# RedLightFlashlightInsert.net
KiCad netlist of a schematic drawn in EAGLE
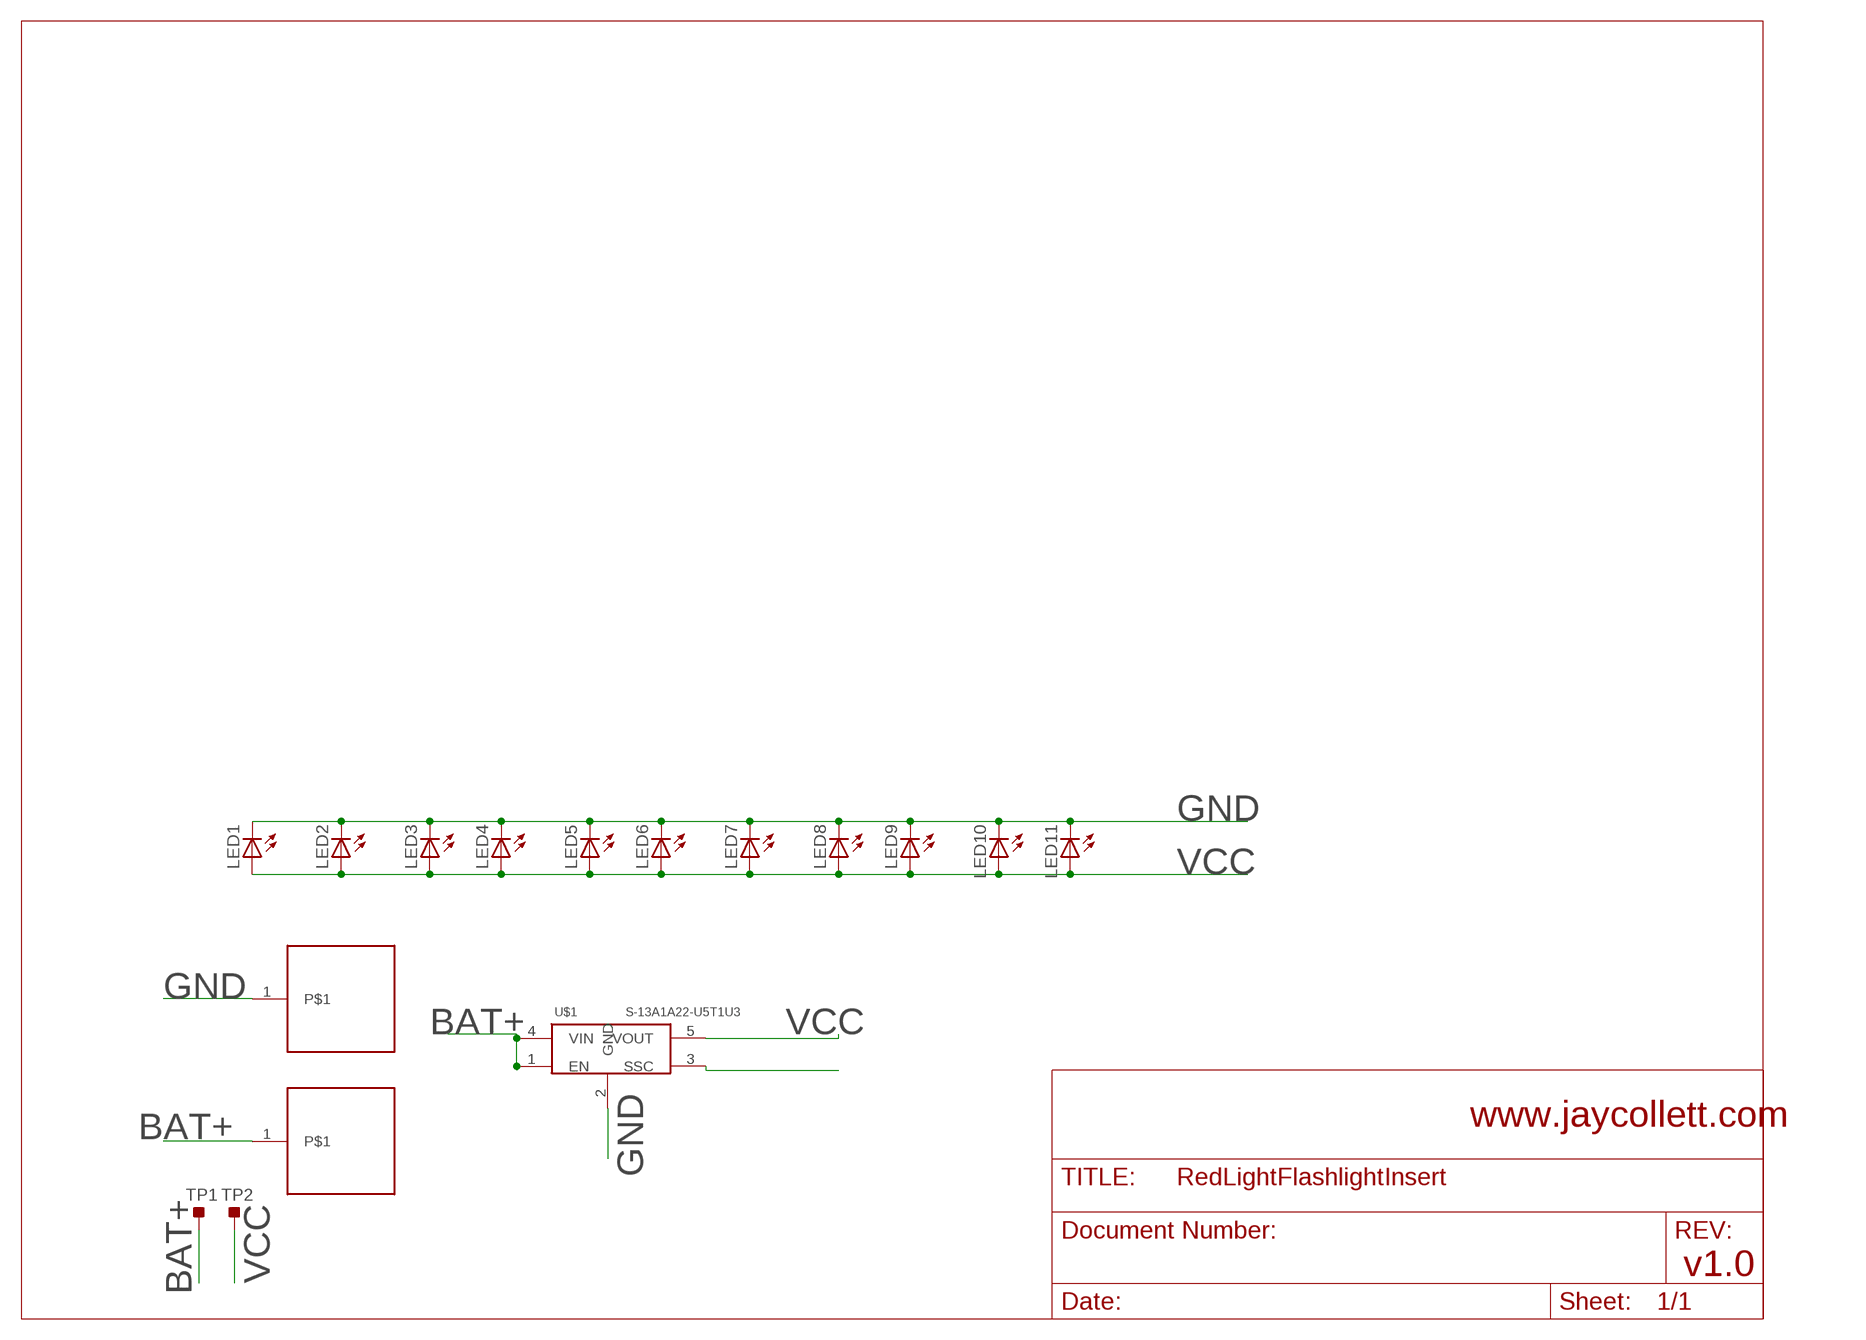
[diagram p0: schematic, sheet 1]

(export (version "E")
  (design (tool "Eeschema 10.0.6"))
  (components
    (comp (ref "LED1")
      (value "LED5MM")
      (footprint "eagle-import:LED5MM")
      (libsource (lib "eagle-import") (part "LED5MM"))
    )
    (comp (ref "LED2")
      (value "LED5MM")
      (footprint "eagle-import:LED5MM")
      (libsource (lib "eagle-import") (part "LED5MM"))
    )
    (comp (ref "LED3")
      (value "LED5MM")
      (footprint "eagle-import:LED5MM")
      (libsource (lib "eagle-import") (part "LED5MM"))
    )
    (comp (ref "LED4")
      (value "LED5MM")
      (footprint "eagle-import:LED5MM")
      (libsource (lib "eagle-import") (part "LED5MM"))
    )
    (comp (ref "LED5")
      (value "LED5MM")
      (footprint "eagle-import:LED5MM")
      (libsource (lib "eagle-import") (part "LED5MM"))
    )
    (comp (ref "LED6")
      (value "LED5MM")
      (footprint "eagle-import:LED5MM")
      (libsource (lib "eagle-import") (part "LED5MM"))
    )
    (comp (ref "LED7")
      (value "LED5MM")
      (footprint "eagle-import:LED5MM")
      (libsource (lib "eagle-import") (part "LED5MM"))
    )
    (comp (ref "LED8")
      (value "LED5MM")
      (footprint "eagle-import:LED5MM")
      (libsource (lib "eagle-import") (part "LED5MM"))
    )
    (comp (ref "LED9")
      (value "LED5MM")
      (footprint "eagle-import:LED5MM")
      (libsource (lib "eagle-import") (part "LED5MM"))
    )
    (comp (ref "LED10")
      (value "LED5MM")
      (footprint "eagle-import:LED5MM")
      (libsource (lib "eagle-import") (part "LED5MM"))
    )
    (comp (ref "LED11")
      (value "LED5MM")
      (footprint "eagle-import:LED5MM")
      (libsource (lib "eagle-import") (part "LED5MM"))
    )
    (comp (ref "TP1")
      (value "TESTPOINT_TPS-SMD-10SN")
      (footprint "eagle-import:TESTPOINT_SMD-10SN")
      (libsource (lib "eagle-import") (part "TESTPOINT_TPS-SMD-10SN"))
    )
    (comp (ref "TP2")
      (value "TESTPOINT_TPS-SMD-10SN")
      (footprint "eagle-import:TESTPOINT_SMD-10SN")
      (libsource (lib "eagle-import") (part "TESTPOINT_TPS-SMD-10SN"))
    )
    (comp (ref "U$1")
      (value "S-13A1A22-U5T1U3")
      (footprint "eagle-import:SOT-89-5")
      (libsource (lib "eagle-import") (part "S-13A1A22-U5T1U3"))
    )
    (comp (ref "U$2")
      (value "SOLDERPAD")
      (footprint "eagle-import:SOLDERPAD")
      (libsource (lib "eagle-import") (part "SOLDERPAD"))
    )
    (comp (ref "U$3")
      (value "SOLDERPAD")
      (footprint "eagle-import:SOLDERPAD")
      (libsource (lib "eagle-import") (part "SOLDERPAD"))
    )
  )
  (nets
    (net (code "1") (name "/BAT+") (class "Default")
      (node (ref "TP1") (pin "TP") (pinfunction "TP_TP") (pintype "passive"))
      (node (ref "U$1") (pin "1") (pinfunction "EN_1") (pintype "input"))
      (node (ref "U$1") (pin "4") (pinfunction "VIN_4") (pintype "power_in"))
      (node (ref "U$3") (pin "1") (pinfunction "P$1_1") (pintype "bidirectional"))
    )
    (net (code "2") (name "/GND") (class "Default")
      (node (ref "LED1") (pin "K") (pinfunction "C_K") (pintype "passive"))
      (node (ref "LED10") (pin "K") (pinfunction "C_K") (pintype "passive"))
      (node (ref "LED11") (pin "K") (pinfunction "C_K") (pintype "passive"))
      (node (ref "LED2") (pin "K") (pinfunction "C_K") (pintype "passive"))
      (node (ref "LED3") (pin "K") (pinfunction "C_K") (pintype "passive"))
      (node (ref "LED4") (pin "K") (pinfunction "C_K") (pintype "passive"))
      (node (ref "LED5") (pin "K") (pinfunction "C_K") (pintype "passive"))
      (node (ref "LED6") (pin "K") (pinfunction "C_K") (pintype "passive"))
      (node (ref "LED7") (pin "K") (pinfunction "C_K") (pintype "passive"))
      (node (ref "LED8") (pin "K") (pinfunction "C_K") (pintype "passive"))
      (node (ref "LED9") (pin "K") (pinfunction "C_K") (pintype "passive"))
      (node (ref "U$1") (pin "2") (pinfunction "GND_2") (pintype "input"))
      (node (ref "U$2") (pin "1") (pinfunction "P$1_1") (pintype "bidirectional"))
    )
    (net (code "3") (name "/VCC") (class "Default")
      (node (ref "LED1") (pin "A") (pinfunction "A_A") (pintype "passive"))
      (node (ref "LED10") (pin "A") (pinfunction "A_A") (pintype "passive"))
      (node (ref "LED11") (pin "A") (pinfunction "A_A") (pintype "passive"))
      (node (ref "LED2") (pin "A") (pinfunction "A_A") (pintype "passive"))
      (node (ref "LED3") (pin "A") (pinfunction "A_A") (pintype "passive"))
      (node (ref "LED4") (pin "A") (pinfunction "A_A") (pintype "passive"))
      (node (ref "LED5") (pin "A") (pinfunction "A_A") (pintype "passive"))
      (node (ref "LED6") (pin "A") (pinfunction "A_A") (pintype "passive"))
      (node (ref "LED7") (pin "A") (pinfunction "A_A") (pintype "passive"))
      (node (ref "LED8") (pin "A") (pinfunction "A_A") (pintype "passive"))
      (node (ref "LED9") (pin "A") (pinfunction "A_A") (pintype "passive"))
      (node (ref "TP2") (pin "TP") (pinfunction "TP_TP") (pintype "passive"))
      (node (ref "U$1") (pin "5") (pinfunction "VOUT_5") (pintype "output"))
    )
    (net (code "4") (name "unconnected-(U$1-SSC-Pad3)") (class "Default")
      (node (ref "U$1") (pin "3") (pinfunction "SSC_3") (pintype "input"))
    )
  )
)
